# MCU_sensor_peripherial.net
KiCad netlist of a schematic drawn in Altium Designer
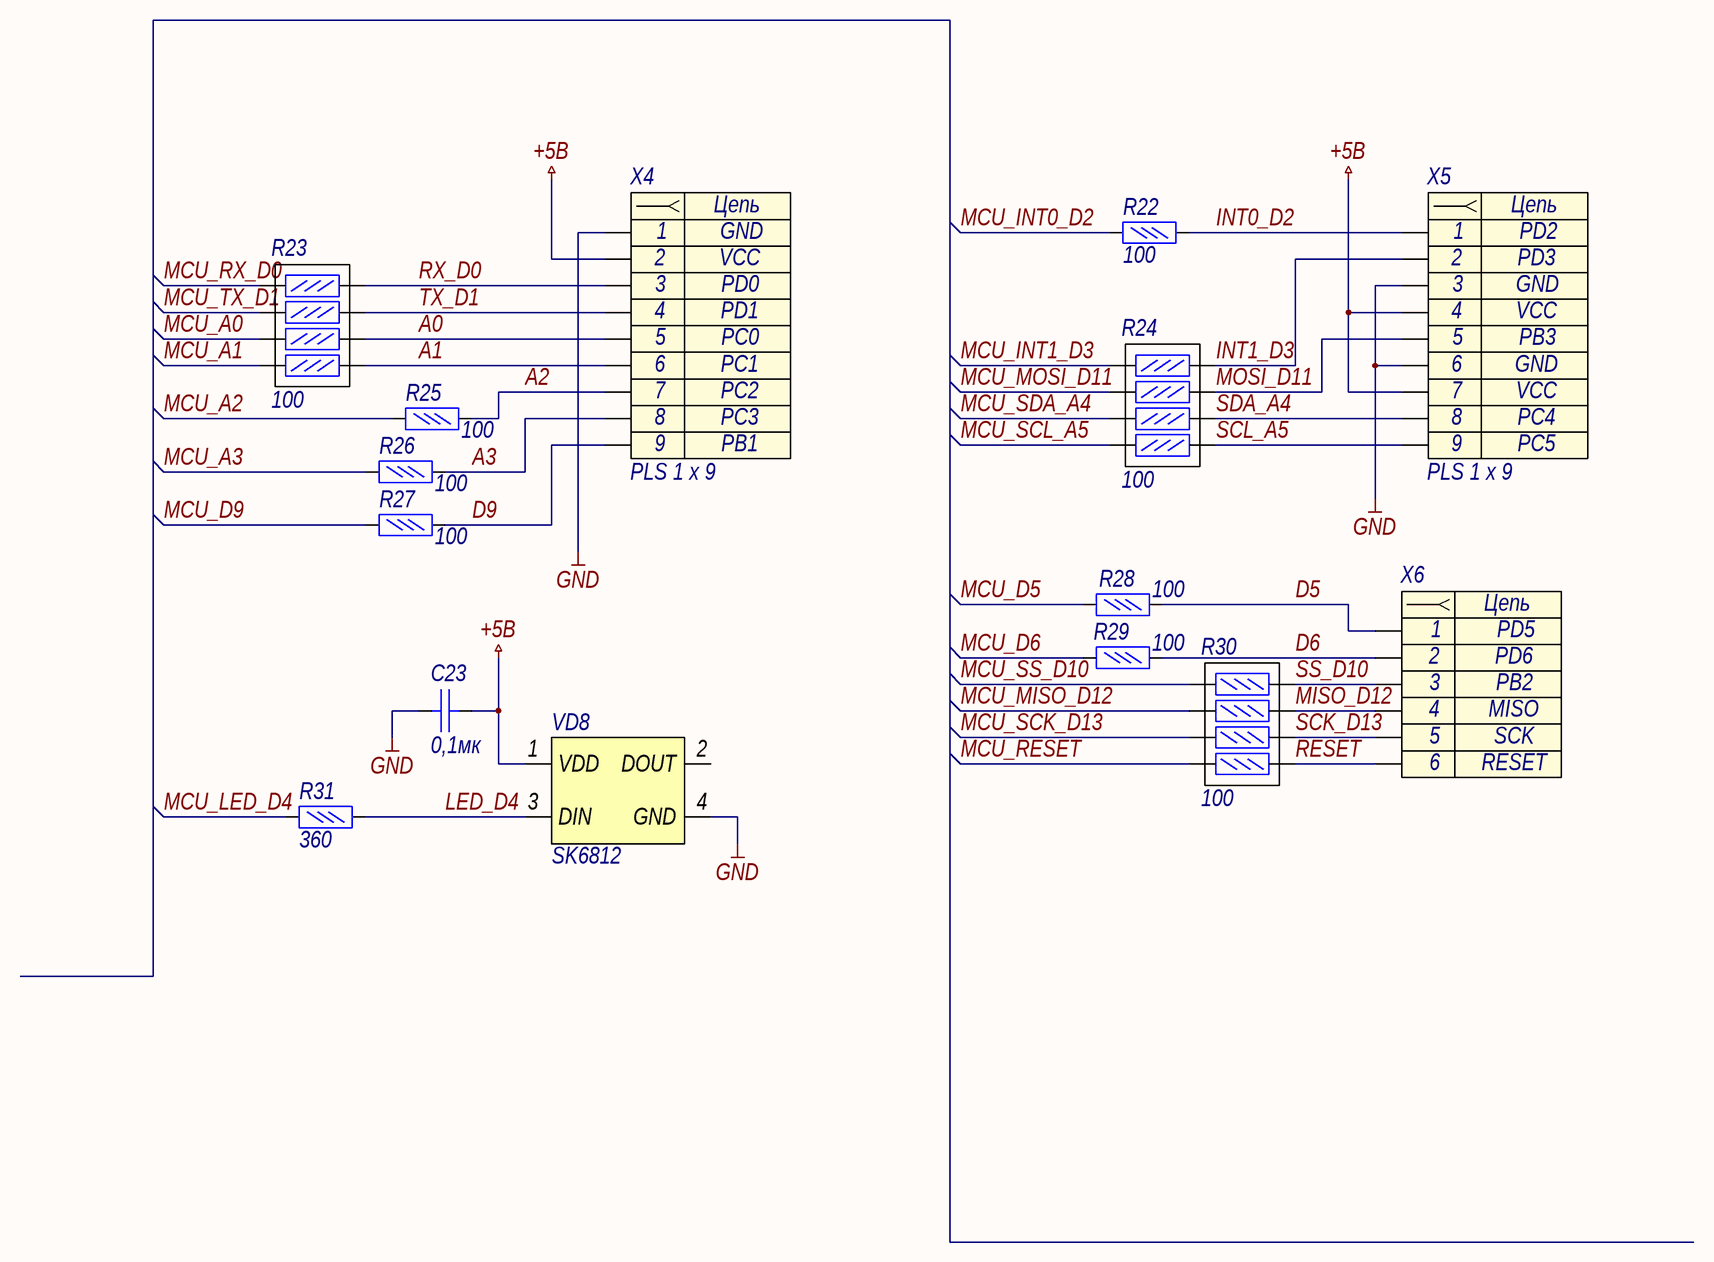
[diagram p0: MCU_sensor_peripherial.SchDoc]

(export (version "E")
  (design (tool "Eeschema 10.0.6"))
  (components
    (comp (ref "R22")
      (value "100")
      (footprint "R0402")
      (description "Резистор 0,05Вт")
      (libsource (lib "MZBT_SchLibrary") (part "Резистор 0.05Вт"))
    )
    (comp (ref "R23")
      (value "100")
      (footprint "R0402x4")
      (libsource (lib "MZBT_SchLibrary") (part "Резисторная сборка 0.05 x 4"))
    )
    (comp (ref "R24")
      (value "100")
      (footprint "R0402x4")
      (libsource (lib "MZBT_SchLibrary") (part "Резисторная сборка 0.05 x 4"))
    )
    (comp (ref "R25")
      (value "100")
      (footprint "R0402")
      (description "Резистор 0,05Вт")
      (libsource (lib "MZBT_SchLibrary") (part "Резистор 0.05Вт"))
    )
    (comp (ref "R26")
      (value "100")
      (footprint "R0402")
      (description "Резистор 0,05Вт")
      (libsource (lib "MZBT_SchLibrary") (part "Резистор 0.05Вт"))
    )
    (comp (ref "R27")
      (value "100")
      (footprint "R0402")
      (description "Резистор 0,05Вт")
      (libsource (lib "MZBT_SchLibrary") (part "Резистор 0.05Вт"))
    )
    (comp (ref "R28")
      (value "100")
      (footprint "R0402")
      (description "Резистор 0,05Вт")
      (libsource (lib "MZBT_SchLibrary") (part "Резистор 0.05Вт"))
    )
    (comp (ref "R29")
      (value "100")
      (footprint "R0402")
      (description "Резистор 0,05Вт")
      (libsource (lib "MZBT_SchLibrary") (part "Резистор 0.05Вт"))
    )
    (comp (ref "R30")
      (value "100")
      (footprint "R0402x4")
      (libsource (lib "") (part "Резисторная сборка 0.05 x 4_1"))
    )
    (comp (ref "R31")
      (value "360")
      (footprint "R0402")
      (description "Резистор 0,05Вт")
      (libsource (lib "MZBT_SchLibrary") (part "Резистор 0.05Вт"))
    )
    (comp (ref "VD8")
      (value "SK6812")
      (footprint "3535")
      (description "светодиод с пиксельной адресацией SK6812 4020")
      (libsource (lib "MZBT_SchLibrary") (part "SK6812"))
    )
    (comp (ref "X4")
      (value "PLS 1 x 9")
      (footprint "PLS2-9 - emty")
      (libsource (lib "MZBT_SchLibrary") (part "PLS 1 x 9"))
    )
    (comp (ref "X5")
      (value "PLS 1 x 9")
      (footprint "PLS2-9 - emty")
      (libsource (lib "MZBT_SchLibrary") (part "PLS 1 x 9"))
    )
    (comp (ref "X6")
      (value "~")
      (footprint "PLS2-6 - emty")
      (libsource (lib "MZBT_SchLibrary") (part "PLS 1 x 6"))
    )
    (comp (ref "С23")
      (value "0,1мк")
      (footprint "C0402")
      (libsource (lib "MZBT_SchLibrary") (part "Кер. конденсатор"))
    )
  )
  (nets
    (net (code "1") (name "+5В") (class "Default")
      (node (ref "VD8") (pin "1") (pinfunction "VDD_1") (pintype "passive"))
      (node (ref "X4") (pin "2") (pinfunction "2_2") (pintype "passive"))
      (node (ref "X5") (pin "4") (pinfunction "4_4") (pintype "passive"))
      (node (ref "X5") (pin "7") (pinfunction "7_7") (pintype "passive"))
      (node (ref "С23") (pin "2") (pinfunction "2_2") (pintype "passive"))
    )
    (net (code "2") (name "/A0") (class "Default")
      (node (ref "R23") (pin "5") (pinfunction "5_5") (pintype "passive"))
      (node (ref "X4") (pin "5") (pinfunction "5_5") (pintype "passive"))
    )
    (net (code "3") (name "/A1") (class "Default")
      (node (ref "R23") (pin "7") (pinfunction "7_7") (pintype "passive"))
      (node (ref "X4") (pin "6") (pinfunction "6_6") (pintype "passive"))
    )
    (net (code "4") (name "/A2") (class "Default")
      (node (ref "R25") (pin "2") (pinfunction "2_2") (pintype "passive"))
      (node (ref "X4") (pin "7") (pinfunction "7_7") (pintype "passive"))
    )
    (net (code "5") (name "/A3") (class "Default")
      (node (ref "R26") (pin "2") (pinfunction "2_2") (pintype "passive"))
      (node (ref "X4") (pin "8") (pinfunction "8_8") (pintype "passive"))
    )
    (net (code "6") (name "/D5") (class "Default")
      (node (ref "R28") (pin "2") (pinfunction "2_2") (pintype "passive"))
      (node (ref "X6") (pin "1") (pinfunction "1_1") (pintype "passive"))
    )
    (net (code "7") (name "/D6") (class "Default")
      (node (ref "R29") (pin "2") (pinfunction "2_2") (pintype "passive"))
      (node (ref "X6") (pin "2") (pinfunction "2_2") (pintype "passive"))
    )
    (net (code "8") (name "/D9") (class "Default")
      (node (ref "R27") (pin "2") (pinfunction "2_2") (pintype "passive"))
      (node (ref "X4") (pin "9") (pinfunction "9_9") (pintype "passive"))
    )
    (net (code "9") (name "/INT0_D2") (class "Default")
      (node (ref "R22") (pin "2") (pinfunction "2_2") (pintype "passive"))
      (node (ref "X5") (pin "1") (pinfunction "1_1") (pintype "passive"))
    )
    (net (code "10") (name "/INT1_D3") (class "Default")
      (node (ref "R24") (pin "1") (pinfunction "1_1") (pintype "passive"))
      (node (ref "X5") (pin "2") (pinfunction "2_2") (pintype "passive"))
    )
    (net (code "11") (name "/LED_D4") (class "Default")
      (node (ref "R31") (pin "2") (pinfunction "2_2") (pintype "passive"))
      (node (ref "VD8") (pin "3") (pinfunction "DIN_3") (pintype "passive"))
    )
    (net (code "12") (name "/MCU_A0") (class "Default")
      (node (ref "R23") (pin "6") (pinfunction "6_6") (pintype "passive"))
    )
    (net (code "13") (name "/MCU_A1") (class "Default")
      (node (ref "R23") (pin "8") (pinfunction "8_8") (pintype "passive"))
    )
    (net (code "14") (name "/MCU_A2") (class "Default")
      (node (ref "R25") (pin "1") (pinfunction "1_1") (pintype "passive"))
    )
    (net (code "15") (name "/MCU_A3") (class "Default")
      (node (ref "R26") (pin "1") (pinfunction "1_1") (pintype "passive"))
    )
    (net (code "16") (name "/MCU_D5") (class "Default")
      (node (ref "R28") (pin "1") (pinfunction "1_1") (pintype "passive"))
    )
    (net (code "17") (name "/MCU_D6") (class "Default")
      (node (ref "R29") (pin "1") (pinfunction "1_1") (pintype "passive"))
    )
    (net (code "18") (name "/MCU_D9") (class "Default")
      (node (ref "R27") (pin "1") (pinfunction "1_1") (pintype "passive"))
    )
    (net (code "19") (name "/MCU_INT0_D2") (class "Default")
      (node (ref "R22") (pin "1") (pinfunction "1_1") (pintype "passive"))
    )
    (net (code "20") (name "/MCU_INT1_D3") (class "Default")
      (node (ref "R24") (pin "2") (pinfunction "2_2") (pintype "passive"))
    )
    (net (code "21") (name "/MCU_LED_D4") (class "Default")
      (node (ref "R31") (pin "1") (pinfunction "1_1") (pintype "passive"))
    )
    (net (code "22") (name "/MCU_MISO_D12") (class "Default")
      (node (ref "R30") (pin "3") (pinfunction "3_3") (pintype "passive"))
    )
    (net (code "23") (name "/MCU_MOSI_D11") (class "Default")
      (node (ref "R24") (pin "4") (pinfunction "4_4") (pintype "passive"))
    )
    (net (code "24") (name "/MCU_RESET") (class "Default")
      (node (ref "R30") (pin "7") (pinfunction "7_7") (pintype "passive"))
    )
    (net (code "25") (name "/MCU_RX_D0") (class "Default")
      (node (ref "R23") (pin "2") (pinfunction "2_2") (pintype "passive"))
    )
    (net (code "26") (name "/MCU_SCK_D13") (class "Default")
      (node (ref "R30") (pin "5") (pinfunction "5_5") (pintype "passive"))
    )
    (net (code "27") (name "/MCU_SCL_A5") (class "Default")
      (node (ref "R24") (pin "8") (pinfunction "8_8") (pintype "passive"))
    )
    (net (code "28") (name "/MCU_SDA_A4") (class "Default")
      (node (ref "R24") (pin "6") (pinfunction "6_6") (pintype "passive"))
    )
    (net (code "29") (name "/MCU_SS_D10") (class "Default")
      (node (ref "R30") (pin "1") (pinfunction "1_1") (pintype "passive"))
    )
    (net (code "30") (name "/MCU_TX_D1") (class "Default")
      (node (ref "R23") (pin "4") (pinfunction "4_4") (pintype "passive"))
    )
    (net (code "31") (name "/MISO_D12") (class "Default")
      (node (ref "R30") (pin "4") (pinfunction "4_4") (pintype "passive"))
      (node (ref "X6") (pin "4") (pinfunction "4_4") (pintype "passive"))
    )
    (net (code "32") (name "/MOSI_D11") (class "Default")
      (node (ref "R24") (pin "3") (pinfunction "3_3") (pintype "passive"))
      (node (ref "X5") (pin "5") (pinfunction "5_5") (pintype "passive"))
    )
    (net (code "33") (name "/RESET") (class "Default")
      (node (ref "R30") (pin "8") (pinfunction "8_8") (pintype "passive"))
      (node (ref "X6") (pin "6") (pinfunction "6_6") (pintype "passive"))
    )
    (net (code "34") (name "/RX_D0") (class "Default")
      (node (ref "R23") (pin "1") (pinfunction "1_1") (pintype "passive"))
      (node (ref "X4") (pin "3") (pinfunction "3_3") (pintype "passive"))
    )
    (net (code "35") (name "/SCK_D13") (class "Default")
      (node (ref "R30") (pin "6") (pinfunction "6_6") (pintype "passive"))
      (node (ref "X6") (pin "5") (pinfunction "5_5") (pintype "passive"))
    )
    (net (code "36") (name "/SCL_A5") (class "Default")
      (node (ref "R24") (pin "7") (pinfunction "7_7") (pintype "passive"))
      (node (ref "X5") (pin "9") (pinfunction "9_9") (pintype "passive"))
    )
    (net (code "37") (name "/SDA_A4") (class "Default")
      (node (ref "R24") (pin "5") (pinfunction "5_5") (pintype "passive"))
      (node (ref "X5") (pin "8") (pinfunction "8_8") (pintype "passive"))
    )
    (net (code "38") (name "/SS_D10") (class "Default")
      (node (ref "R30") (pin "2") (pinfunction "2_2") (pintype "passive"))
      (node (ref "X6") (pin "3") (pinfunction "3_3") (pintype "passive"))
    )
    (net (code "39") (name "/TX_D1") (class "Default")
      (node (ref "R23") (pin "3") (pinfunction "3_3") (pintype "passive"))
      (node (ref "X4") (pin "4") (pinfunction "4_4") (pintype "passive"))
    )
    (net (code "40") (name "GND") (class "Default")
      (node (ref "VD8") (pin "4") (pinfunction "GND_4") (pintype "passive"))
      (node (ref "X4") (pin "1") (pinfunction "1_1") (pintype "passive"))
      (node (ref "X5") (pin "3") (pinfunction "3_3") (pintype "passive"))
      (node (ref "X5") (pin "6") (pinfunction "6_6") (pintype "passive"))
      (node (ref "С23") (pin "1") (pinfunction "1_1") (pintype "passive"))
    )
    (net (code "41") (name "unconnected-(VD8-DOUT-Pad2)") (class "Default")
      (node (ref "VD8") (pin "2") (pinfunction "DOUT_2") (pintype "passive"))
    )
  )
)
